# button8x-analog-v1.net
KiCad netlist of a schematic drawn in EAGLE
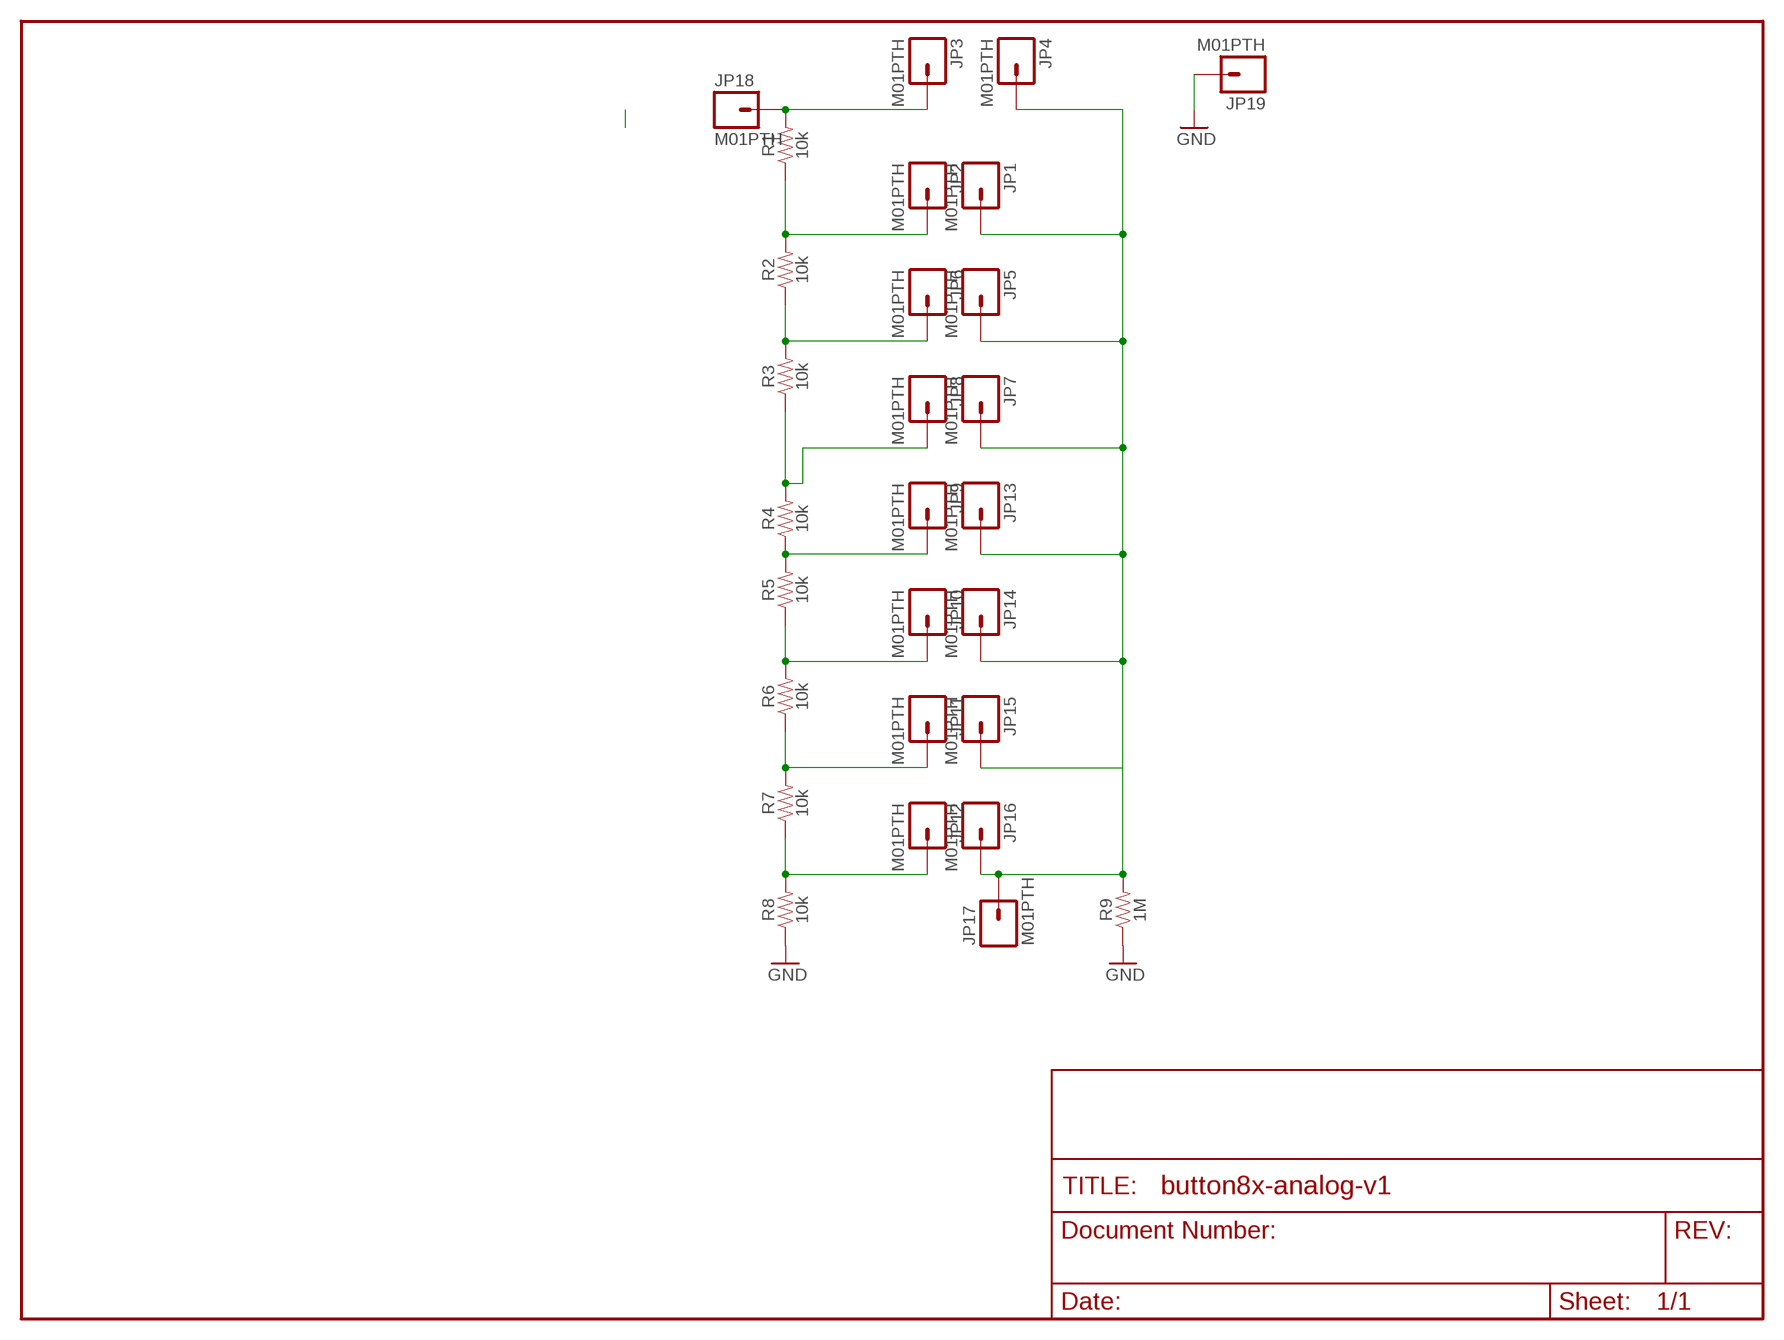
[diagram p0: schematic, sheet 1]

(export (version "E")
  (design (tool "Eeschema 10.0.6"))
  (components
    (comp (ref "JP1")
      (value "M01PTH")
      (footprint "eagle-import:1X01")
      (libsource (lib "eagle-import") (part "M01PTH"))
    )
    (comp (ref "JP2")
      (value "M01PTH")
      (footprint "eagle-import:1X01")
      (libsource (lib "eagle-import") (part "M01PTH"))
    )
    (comp (ref "JP3")
      (value "M01PTH")
      (footprint "eagle-import:1X01")
      (libsource (lib "eagle-import") (part "M01PTH"))
    )
    (comp (ref "JP4")
      (value "M01PTH")
      (footprint "eagle-import:1X01")
      (libsource (lib "eagle-import") (part "M01PTH"))
    )
    (comp (ref "JP5")
      (value "M01PTH")
      (footprint "eagle-import:1X01")
      (libsource (lib "eagle-import") (part "M01PTH"))
    )
    (comp (ref "JP6")
      (value "M01PTH")
      (footprint "eagle-import:1X01")
      (libsource (lib "eagle-import") (part "M01PTH"))
    )
    (comp (ref "JP7")
      (value "M01PTH")
      (footprint "eagle-import:1X01")
      (libsource (lib "eagle-import") (part "M01PTH"))
    )
    (comp (ref "JP8")
      (value "M01PTH")
      (footprint "eagle-import:1X01")
      (libsource (lib "eagle-import") (part "M01PTH"))
    )
    (comp (ref "JP9")
      (value "M01PTH")
      (footprint "eagle-import:1X01")
      (libsource (lib "eagle-import") (part "M01PTH"))
    )
    (comp (ref "JP10")
      (value "M01PTH")
      (footprint "eagle-import:1X01")
      (libsource (lib "eagle-import") (part "M01PTH"))
    )
    (comp (ref "JP11")
      (value "M01PTH")
      (footprint "eagle-import:1X01")
      (libsource (lib "eagle-import") (part "M01PTH"))
    )
    (comp (ref "JP12")
      (value "M01PTH")
      (footprint "eagle-import:1X01")
      (libsource (lib "eagle-import") (part "M01PTH"))
    )
    (comp (ref "JP13")
      (value "M01PTH")
      (footprint "eagle-import:1X01")
      (libsource (lib "eagle-import") (part "M01PTH"))
    )
    (comp (ref "JP14")
      (value "M01PTH")
      (footprint "eagle-import:1X01")
      (libsource (lib "eagle-import") (part "M01PTH"))
    )
    (comp (ref "JP15")
      (value "M01PTH")
      (footprint "eagle-import:1X01")
      (libsource (lib "eagle-import") (part "M01PTH"))
    )
    (comp (ref "JP16")
      (value "M01PTH")
      (footprint "eagle-import:1X01")
      (libsource (lib "eagle-import") (part "M01PTH"))
    )
    (comp (ref "JP17")
      (value "M01PTH")
      (footprint "eagle-import:1X01")
      (libsource (lib "eagle-import") (part "M01PTH"))
    )
    (comp (ref "JP18")
      (value "M01PTH")
      (footprint "eagle-import:1X01")
      (libsource (lib "eagle-import") (part "M01PTH"))
    )
    (comp (ref "JP19")
      (value "M01PTH")
      (footprint "eagle-import:1X01")
      (libsource (lib "eagle-import") (part "M01PTH"))
    )
    (comp (ref "R1")
      (value "10k")
      (footprint "eagle-import:0603")
      (libsource (lib "eagle-import") (part "10KOHM-0603-1/10W-1%"))
    )
    (comp (ref "R2")
      (value "10k")
      (footprint "eagle-import:0603")
      (libsource (lib "eagle-import") (part "10KOHM-0603-1/10W-1%"))
    )
    (comp (ref "R3")
      (value "10k")
      (footprint "eagle-import:0603")
      (libsource (lib "eagle-import") (part "10KOHM-0603-1/10W-1%"))
    )
    (comp (ref "R4")
      (value "10k")
      (footprint "eagle-import:0603")
      (libsource (lib "eagle-import") (part "10KOHM-0603-1/10W-1%"))
    )
    (comp (ref "R5")
      (value "10k")
      (footprint "eagle-import:0603")
      (libsource (lib "eagle-import") (part "10KOHM-0603-1/10W-1%"))
    )
    (comp (ref "R6")
      (value "10k")
      (footprint "eagle-import:0603")
      (libsource (lib "eagle-import") (part "10KOHM-0603-1/10W-1%"))
    )
    (comp (ref "R7")
      (value "10k")
      (footprint "eagle-import:0603")
      (libsource (lib "eagle-import") (part "10KOHM-0603-1/10W-1%"))
    )
    (comp (ref "R8")
      (value "10k")
      (footprint "eagle-import:0603")
      (libsource (lib "eagle-import") (part "10KOHM-0603-1/10W-1%"))
    )
    (comp (ref "R9")
      (value "1M")
      (footprint "eagle-import:0603")
      (libsource (lib "eagle-import") (part "10KOHM-0603-1/10W-1%"))
    )
  )
  (nets
    (net (code "1") (name "GND") (class "Default")
      (node (ref "JP19") (pin "1") (pinfunction "1_1") (pintype "passive"))
      (node (ref "R8") (pin "1") (pinfunction "1_1") (pintype "passive"))
      (node (ref "R9") (pin "1") (pinfunction "1_1") (pintype "passive"))
    )
    (net (code "2") (name "Net-(JP1-Pad1)") (class "Default")
      (node (ref "JP1") (pin "1") (pinfunction "1_1") (pintype "passive"))
      (node (ref "JP13") (pin "1") (pinfunction "1_1") (pintype "passive"))
      (node (ref "JP14") (pin "1") (pinfunction "1_1") (pintype "passive"))
      (node (ref "JP15") (pin "1") (pinfunction "1_1") (pintype "passive"))
      (node (ref "JP16") (pin "1") (pinfunction "1_1") (pintype "passive"))
      (node (ref "JP17") (pin "1") (pinfunction "1_1") (pintype "passive"))
      (node (ref "JP4") (pin "1") (pinfunction "1_1") (pintype "passive"))
      (node (ref "JP5") (pin "1") (pinfunction "1_1") (pintype "passive"))
      (node (ref "JP7") (pin "1") (pinfunction "1_1") (pintype "passive"))
      (node (ref "R9") (pin "2") (pinfunction "2_2") (pintype "passive"))
    )
    (net (code "3") (name "Net-(JP2-Pad1)") (class "Default")
      (node (ref "JP2") (pin "1") (pinfunction "1_1") (pintype "passive"))
      (node (ref "R1") (pin "1") (pinfunction "1_1") (pintype "passive"))
      (node (ref "R2") (pin "2") (pinfunction "2_2") (pintype "passive"))
    )
    (net (code "4") (name "Net-(JP6-Pad1)") (class "Default")
      (node (ref "JP6") (pin "1") (pinfunction "1_1") (pintype "passive"))
      (node (ref "R2") (pin "1") (pinfunction "1_1") (pintype "passive"))
      (node (ref "R3") (pin "2") (pinfunction "2_2") (pintype "passive"))
    )
    (net (code "5") (name "Net-(JP8-Pad1)") (class "Default")
      (node (ref "JP8") (pin "1") (pinfunction "1_1") (pintype "passive"))
      (node (ref "R3") (pin "1") (pinfunction "1_1") (pintype "passive"))
      (node (ref "R4") (pin "2") (pinfunction "2_2") (pintype "passive"))
    )
    (net (code "6") (name "Net-(JP9-Pad1)") (class "Default")
      (node (ref "JP9") (pin "1") (pinfunction "1_1") (pintype "passive"))
      (node (ref "R4") (pin "1") (pinfunction "1_1") (pintype "passive"))
      (node (ref "R5") (pin "2") (pinfunction "2_2") (pintype "passive"))
    )
    (net (code "7") (name "Net-(JP10-Pad1)") (class "Default")
      (node (ref "JP10") (pin "1") (pinfunction "1_1") (pintype "passive"))
      (node (ref "R5") (pin "1") (pinfunction "1_1") (pintype "passive"))
      (node (ref "R6") (pin "2") (pinfunction "2_2") (pintype "passive"))
    )
    (net (code "8") (name "Net-(JP11-Pad1)") (class "Default")
      (node (ref "JP11") (pin "1") (pinfunction "1_1") (pintype "passive"))
      (node (ref "R6") (pin "1") (pinfunction "1_1") (pintype "passive"))
      (node (ref "R7") (pin "2") (pinfunction "2_2") (pintype "passive"))
    )
    (net (code "9") (name "Net-(JP12-Pad1)") (class "Default")
      (node (ref "JP12") (pin "1") (pinfunction "1_1") (pintype "passive"))
      (node (ref "R7") (pin "1") (pinfunction "1_1") (pintype "passive"))
      (node (ref "R8") (pin "2") (pinfunction "2_2") (pintype "passive"))
    )
    (net (code "10") (name "Net-(JP18-Pad1)") (class "Default")
      (node (ref "JP18") (pin "1") (pinfunction "1_1") (pintype "passive"))
      (node (ref "JP3") (pin "1") (pinfunction "1_1") (pintype "passive"))
      (node (ref "R1") (pin "2") (pinfunction "2_2") (pintype "passive"))
    )
  )
)
